# adc_420.net
KiCad netlist of a schematic drawn in Altium Designer
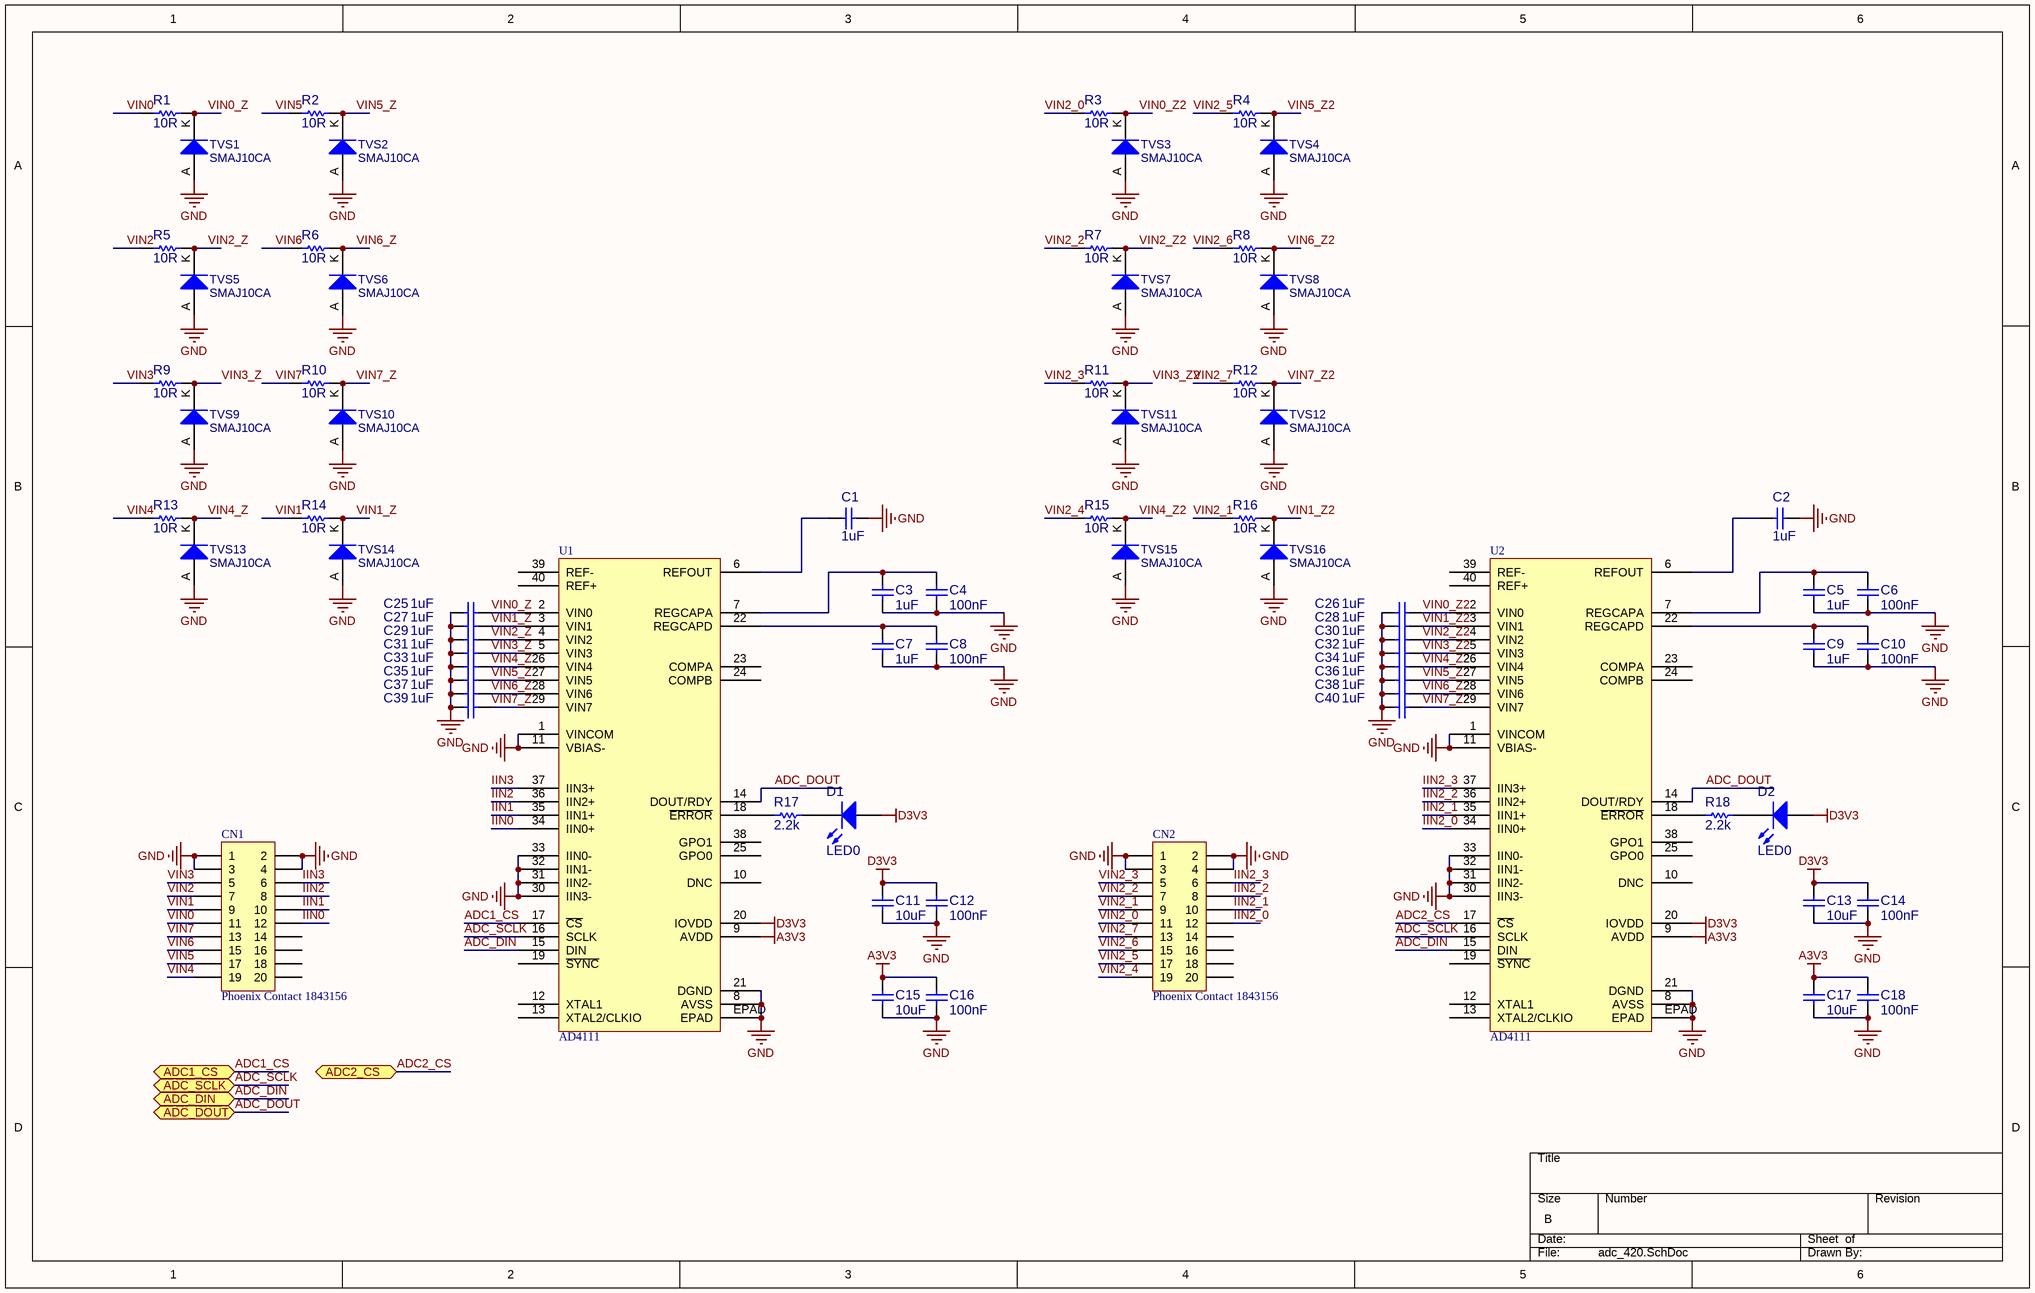
[diagram p0: adc_420.SchDoc]

(export (version "E")
  (design (tool "Eeschema 10.0.6"))
  (components
    (comp (ref "C1")
      (value "1uF")
      (footprint "C0603")
      (description "Capacitor")
      (fields (field (name "PUBLISHER") "Altium Limited"))
      (libsource (lib "Miscellaneous Devices") (part "Cap"))
    )
    (comp (ref "C2")
      (value "1uF")
      (footprint "C0603")
      (description "Capacitor")
      (fields (field (name "PUBLISHER") "Altium Limited"))
      (libsource (lib "Miscellaneous Devices") (part "Cap"))
    )
    (comp (ref "C3")
      (value "1uF")
      (footprint "C0603")
      (description "Capacitor")
      (fields (field (name "PUBLISHER") "Altium Limited"))
      (libsource (lib "Miscellaneous Devices") (part "Cap"))
    )
    (comp (ref "C4")
      (value "100nF")
      (footprint "C0603")
      (description "GRM155R71C104KA88J")
      (fields (field (name "PUBLISHER") "Altium Limited"))
      (libsource (lib "Miscellaneous Devices") (part "Cap"))
    )
    (comp (ref "C5")
      (value "1uF")
      (footprint "C0603")
      (description "Capacitor")
      (fields (field (name "PUBLISHER") "Altium Limited"))
      (libsource (lib "Miscellaneous Devices") (part "Cap"))
    )
    (comp (ref "C6")
      (value "100nF")
      (footprint "C0603")
      (description "GRM155R71C104KA88J")
      (fields (field (name "PUBLISHER") "Altium Limited"))
      (libsource (lib "Miscellaneous Devices") (part "Cap"))
    )
    (comp (ref "C7")
      (value "1uF")
      (footprint "C0603")
      (description "Capacitor")
      (fields (field (name "PUBLISHER") "Altium Limited"))
      (libsource (lib "Miscellaneous Devices") (part "Cap"))
    )
    (comp (ref "C8")
      (value "100nF")
      (footprint "C0603")
      (description "GRM155R71C104KA88J")
      (fields (field (name "PUBLISHER") "Altium Limited"))
      (libsource (lib "Miscellaneous Devices") (part "Cap"))
    )
    (comp (ref "C9")
      (value "1uF")
      (footprint "C0603")
      (description "Capacitor")
      (fields (field (name "PUBLISHER") "Altium Limited"))
      (libsource (lib "Miscellaneous Devices") (part "Cap"))
    )
    (comp (ref "C10")
      (value "100nF")
      (footprint "C0603")
      (description "GRM155R71C104KA88J")
      (fields (field (name "PUBLISHER") "Altium Limited"))
      (libsource (lib "Miscellaneous Devices") (part "Cap"))
    )
    (comp (ref "C11")
      (value "10uF")
      (footprint "C1206N")
      (description "Capacitor")
      (fields (field (name "PUBLISHER") "Altium Limited"))
      (libsource (lib "Miscellaneous Devices") (part "Cap"))
    )
    (comp (ref "C12")
      (value "100nF")
      (footprint "C0603")
      (description "GRM155R71C104KA88J")
      (fields (field (name "PUBLISHER") "Altium Limited"))
      (libsource (lib "Miscellaneous Devices") (part "Cap"))
    )
    (comp (ref "C13")
      (value "10uF")
      (footprint "C1206N")
      (description "Capacitor")
      (fields (field (name "PUBLISHER") "Altium Limited"))
      (libsource (lib "Miscellaneous Devices") (part "Cap"))
    )
    (comp (ref "C14")
      (value "100nF")
      (footprint "C0603")
      (description "GRM155R71C104KA88J")
      (fields (field (name "PUBLISHER") "Altium Limited"))
      (libsource (lib "Miscellaneous Devices") (part "Cap"))
    )
    (comp (ref "C15")
      (value "10uF")
      (footprint "C1206N")
      (description "Capacitor")
      (fields (field (name "PUBLISHER") "Altium Limited"))
      (libsource (lib "Miscellaneous Devices") (part "Cap"))
    )
    (comp (ref "C16")
      (value "100nF")
      (footprint "C0603")
      (description "GRM155R71C104KA88J")
      (fields (field (name "PUBLISHER") "Altium Limited"))
      (libsource (lib "Miscellaneous Devices") (part "Cap"))
    )
    (comp (ref "C17")
      (value "10uF")
      (footprint "C1206N")
      (description "Capacitor")
      (fields (field (name "PUBLISHER") "Altium Limited"))
      (libsource (lib "Miscellaneous Devices") (part "Cap"))
    )
    (comp (ref "C18")
      (value "100nF")
      (footprint "C0603")
      (description "GRM155R71C104KA88J")
      (fields (field (name "PUBLISHER") "Altium Limited"))
      (libsource (lib "Miscellaneous Devices") (part "Cap"))
    )
    (comp (ref "C25")
      (value "1uF")
      (footprint "C0603")
      (description "Capacitor")
      (fields (field (name "PUBLISHER") "Altium Limited"))
      (libsource (lib "Miscellaneous Devices") (part "Cap"))
    )
    (comp (ref "C26")
      (value "1uF")
      (footprint "C0603")
      (description "Capacitor")
      (fields (field (name "PUBLISHER") "Altium Limited"))
      (libsource (lib "Miscellaneous Devices") (part "Cap"))
    )
    (comp (ref "C27")
      (value "1uF")
      (footprint "C0603")
      (description "Capacitor")
      (fields (field (name "PUBLISHER") "Altium Limited"))
      (libsource (lib "Miscellaneous Devices") (part "Cap"))
    )
    (comp (ref "C28")
      (value "1uF")
      (footprint "C0603")
      (description "Capacitor")
      (fields (field (name "PUBLISHER") "Altium Limited"))
      (libsource (lib "Miscellaneous Devices") (part "Cap"))
    )
    (comp (ref "C29")
      (value "1uF")
      (footprint "C0603")
      (description "Capacitor")
      (fields (field (name "PUBLISHER") "Altium Limited"))
      (libsource (lib "Miscellaneous Devices") (part "Cap"))
    )
    (comp (ref "C30")
      (value "1uF")
      (footprint "C0603")
      (description "Capacitor")
      (fields (field (name "PUBLISHER") "Altium Limited"))
      (libsource (lib "Miscellaneous Devices") (part "Cap"))
    )
    (comp (ref "C31")
      (value "1uF")
      (footprint "C0603")
      (description "Capacitor")
      (fields (field (name "PUBLISHER") "Altium Limited"))
      (libsource (lib "Miscellaneous Devices") (part "Cap"))
    )
    (comp (ref "C32")
      (value "1uF")
      (footprint "C0603")
      (description "Capacitor")
      (fields (field (name "PUBLISHER") "Altium Limited"))
      (libsource (lib "Miscellaneous Devices") (part "Cap"))
    )
    (comp (ref "C33")
      (value "1uF")
      (footprint "C0603")
      (description "Capacitor")
      (fields (field (name "PUBLISHER") "Altium Limited"))
      (libsource (lib "Miscellaneous Devices") (part "Cap"))
    )
    (comp (ref "C34")
      (value "1uF")
      (footprint "C0603")
      (description "Capacitor")
      (fields (field (name "PUBLISHER") "Altium Limited"))
      (libsource (lib "Miscellaneous Devices") (part "Cap"))
    )
    (comp (ref "C35")
      (value "1uF")
      (footprint "C0603")
      (description "Capacitor")
      (fields (field (name "PUBLISHER") "Altium Limited"))
      (libsource (lib "Miscellaneous Devices") (part "Cap"))
    )
    (comp (ref "C36")
      (value "1uF")
      (footprint "C0603")
      (description "Capacitor")
      (fields (field (name "PUBLISHER") "Altium Limited"))
      (libsource (lib "Miscellaneous Devices") (part "Cap"))
    )
    (comp (ref "C37")
      (value "1uF")
      (footprint "C0603")
      (description "Capacitor")
      (fields (field (name "PUBLISHER") "Altium Limited"))
      (libsource (lib "Miscellaneous Devices") (part "Cap"))
    )
    (comp (ref "C38")
      (value "1uF")
      (footprint "C0603")
      (description "Capacitor")
      (fields (field (name "PUBLISHER") "Altium Limited"))
      (libsource (lib "Miscellaneous Devices") (part "Cap"))
    )
    (comp (ref "C39")
      (value "1uF")
      (footprint "C0603")
      (description "Capacitor")
      (fields (field (name "PUBLISHER") "Altium Limited"))
      (libsource (lib "Miscellaneous Devices") (part "Cap"))
    )
    (comp (ref "C40")
      (value "1uF")
      (footprint "C0603")
      (description "Capacitor")
      (fields (field (name "PUBLISHER") "Altium Limited"))
      (libsource (lib "Miscellaneous Devices") (part "Cap"))
    )
    (comp (ref "CN1")
      (value "Phoenix Contact 1843156")
      (footprint "PHOENIX1843156")
      (description "Header, 10-Pin, Dual row")
      (fields (field (name "PUBLISHER") "Altium Limited"))
      (libsource (lib "Miscellaneous Connectors") (part "Header 10X2"))
    )
    (comp (ref "CN2")
      (value "Phoenix Contact 1843156")
      (footprint "PHOENIX1843156")
      (description "Header, 10-Pin, Dual row")
      (fields (field (name "PUBLISHER") "Altium Limited"))
      (libsource (lib "Miscellaneous Connectors") (part "Header 10X2"))
    )
    (comp (ref "D1")
      (value "LED0")
      (footprint "LED0603")
      (description "Typical INFRARED GaAs LED")
      (fields (field (name "PUBLISHER") "Altium Limited"))
      (libsource (lib "Miscellaneous Devices") (part "LED0"))
    )
    (comp (ref "D2")
      (value "LED0")
      (footprint "LED0603")
      (description "Typical INFRARED GaAs LED")
      (fields (field (name "PUBLISHER") "Altium Limited"))
      (libsource (lib "Miscellaneous Devices") (part "LED0"))
    )
    (comp (ref "R1")
      (value "10R")
      (footprint "R0603")
      (description "Resistor")
      (fields (field (name "PUBLISHER") "Altium Limited"))
      (libsource (lib "Miscellaneous Devices") (part "Res1"))
    )
    (comp (ref "R2")
      (value "10R")
      (footprint "R0603")
      (description "Resistor")
      (fields (field (name "PUBLISHER") "Altium Limited"))
      (libsource (lib "Miscellaneous Devices") (part "Res1"))
    )
    (comp (ref "R3")
      (value "10R")
      (footprint "R0603")
      (description "Resistor")
      (fields (field (name "PUBLISHER") "Altium Limited"))
      (libsource (lib "Miscellaneous Devices") (part "Res1"))
    )
    (comp (ref "R4")
      (value "10R")
      (footprint "R0603")
      (description "Resistor")
      (fields (field (name "PUBLISHER") "Altium Limited"))
      (libsource (lib "Miscellaneous Devices") (part "Res1"))
    )
    (comp (ref "R5")
      (value "10R")
      (footprint "R0603")
      (description "Resistor")
      (fields (field (name "PUBLISHER") "Altium Limited"))
      (libsource (lib "Miscellaneous Devices") (part "Res1"))
    )
    (comp (ref "R6")
      (value "10R")
      (footprint "R0603")
      (description "Resistor")
      (fields (field (name "PUBLISHER") "Altium Limited"))
      (libsource (lib "Miscellaneous Devices") (part "Res1"))
    )
    (comp (ref "R7")
      (value "10R")
      (footprint "R0603")
      (description "Resistor")
      (fields (field (name "PUBLISHER") "Altium Limited"))
      (libsource (lib "Miscellaneous Devices") (part "Res1"))
    )
    (comp (ref "R8")
      (value "10R")
      (footprint "R0603")
      (description "Resistor")
      (fields (field (name "PUBLISHER") "Altium Limited"))
      (libsource (lib "Miscellaneous Devices") (part "Res1"))
    )
    (comp (ref "R9")
      (value "10R")
      (footprint "R0603")
      (description "Resistor")
      (fields (field (name "PUBLISHER") "Altium Limited"))
      (libsource (lib "Miscellaneous Devices") (part "Res1"))
    )
    (comp (ref "R10")
      (value "10R")
      (footprint "R0603")
      (description "Resistor")
      (fields (field (name "PUBLISHER") "Altium Limited"))
      (libsource (lib "Miscellaneous Devices") (part "Res1"))
    )
    (comp (ref "R11")
      (value "10R")
      (footprint "R0603")
      (description "Resistor")
      (fields (field (name "PUBLISHER") "Altium Limited"))
      (libsource (lib "Miscellaneous Devices") (part "Res1"))
    )
    (comp (ref "R12")
      (value "10R")
      (footprint "R0603")
      (description "Resistor")
      (fields (field (name "PUBLISHER") "Altium Limited"))
      (libsource (lib "Miscellaneous Devices") (part "Res1"))
    )
    (comp (ref "R13")
      (value "10R")
      (footprint "R0603")
      (description "Resistor")
      (fields (field (name "PUBLISHER") "Altium Limited"))
      (libsource (lib "Miscellaneous Devices") (part "Res1"))
    )
    (comp (ref "R14")
      (value "10R")
      (footprint "R0603")
      (description "Resistor")
      (fields (field (name "PUBLISHER") "Altium Limited"))
      (libsource (lib "Miscellaneous Devices") (part "Res1"))
    )
    (comp (ref "R15")
      (value "10R")
      (footprint "R0603")
      (description "Resistor")
      (fields (field (name "PUBLISHER") "Altium Limited"))
      (libsource (lib "Miscellaneous Devices") (part "Res1"))
    )
    (comp (ref "R16")
      (value "10R")
      (footprint "R0603")
      (description "Resistor")
      (fields (field (name "PUBLISHER") "Altium Limited"))
      (libsource (lib "Miscellaneous Devices") (part "Res1"))
    )
    (comp (ref "R17")
      (value "2.2k")
      (footprint "R0603")
      (description "Resistor")
      (fields (field (name "PUBLISHER") "Altium Limited"))
      (libsource (lib "Miscellaneous Devices") (part "Res1"))
    )
    (comp (ref "R18")
      (value "2.2k")
      (footprint "R0603")
      (description "Resistor")
      (fields (field (name "PUBLISHER") "Altium Limited"))
      (libsource (lib "Miscellaneous Devices") (part "Res1"))
    )
    (comp (ref "TVS1") (value "SMAJ10CA") (footprint "SMA") (libsource (lib "ADI-MEMs-more") (part "DIODE")))
    (comp (ref "TVS2") (value "SMAJ10CA") (footprint "SMA") (libsource (lib "ADI-MEMs-more") (part "DIODE")))
    (comp (ref "TVS3") (value "SMAJ10CA") (footprint "SMA") (libsource (lib "ADI-MEMs-more") (part "DIODE")))
    (comp (ref "TVS4") (value "SMAJ10CA") (footprint "SMA") (libsource (lib "ADI-MEMs-more") (part "DIODE")))
    (comp (ref "TVS5") (value "SMAJ10CA") (footprint "SMA") (libsource (lib "ADI-MEMs-more") (part "DIODE")))
    (comp (ref "TVS6") (value "SMAJ10CA") (footprint "SMA") (libsource (lib "ADI-MEMs-more") (part "DIODE")))
    (comp (ref "TVS7") (value "SMAJ10CA") (footprint "SMA") (libsource (lib "ADI-MEMs-more") (part "DIODE")))
    (comp (ref "TVS8") (value "SMAJ10CA") (footprint "SMA") (libsource (lib "ADI-MEMs-more") (part "DIODE")))
    (comp (ref "TVS9") (value "SMAJ10CA") (footprint "SMA") (libsource (lib "ADI-MEMs-more") (part "DIODE")))
    (comp (ref "TVS10") (value "SMAJ10CA") (footprint "SMA") (libsource (lib "ADI-MEMs-more") (part "DIODE")))
    (comp (ref "TVS11") (value "SMAJ10CA") (footprint "SMA") (libsource (lib "ADI-MEMs-more") (part "DIODE")))
    (comp (ref "TVS12") (value "SMAJ10CA") (footprint "SMA") (libsource (lib "ADI-MEMs-more") (part "DIODE")))
    (comp (ref "TVS13") (value "SMAJ10CA") (footprint "SMA") (libsource (lib "ADI-MEMs-more") (part "DIODE")))
    (comp (ref "TVS14") (value "SMAJ10CA") (footprint "SMA") (libsource (lib "ADI-MEMs-more") (part "DIODE")))
    (comp (ref "TVS15") (value "SMAJ10CA") (footprint "SMA") (libsource (lib "ADI-MEMs-more") (part "DIODE")))
    (comp (ref "TVS16") (value "SMAJ10CA") (footprint "SMA") (libsource (lib "ADI-MEMs-more") (part "DIODE")))
    (comp (ref "U1")
      (value "AD4111")
      (footprint "AD7119")
      (libsource (lib "PowerComps-more") (part "AD4111"))
    )
    (comp (ref "U2")
      (value "AD4111")
      (footprint "AD7119")
      (libsource (lib "PowerComps-more") (part "AD4111"))
    )
  )
  (nets
    (net (code "1") (name "/ADC1_CS") (class "Default")
      (node (ref "U1") (pin "17") (pinfunction "~{CS}_17") (pintype "passive"))
    )
    (net (code "2") (name "/ADC2_CS") (class "Default")
      (node (ref "U2") (pin "17") (pinfunction "~{CS}_17") (pintype "passive"))
    )
    (net (code "3") (name "/ADC_DIN") (class "Default")
      (node (ref "U1") (pin "15") (pinfunction "DIN_15") (pintype "passive"))
      (node (ref "U2") (pin "15") (pinfunction "DIN_15") (pintype "passive"))
    )
    (net (code "4") (name "/ADC_DOUT") (class "Default")
      (node (ref "U1") (pin "14") (pinfunction "DOUT/RDY_14") (pintype "passive"))
      (node (ref "U2") (pin "14") (pinfunction "DOUT/RDY_14") (pintype "passive"))
    )
    (net (code "5") (name "/ADC_SCLK") (class "Default")
      (node (ref "U1") (pin "16") (pinfunction "SCLK_16") (pintype "passive"))
      (node (ref "U2") (pin "16") (pinfunction "SCLK_16") (pintype "passive"))
    )
    (net (code "6") (name "/IIN0") (class "Default")
      (node (ref "CN1") (pin "12") (pinfunction "12_12") (pintype "passive"))
      (node (ref "U1") (pin "34") (pinfunction "IIN0+_34") (pintype "passive"))
    )
    (net (code "7") (name "/IIN1") (class "Default")
      (node (ref "CN1") (pin "10") (pinfunction "10_10") (pintype "passive"))
      (node (ref "U1") (pin "35") (pinfunction "IIN1+_35") (pintype "passive"))
    )
    (net (code "8") (name "/IIN2") (class "Default")
      (node (ref "CN1") (pin "8") (pinfunction "8_8") (pintype "passive"))
      (node (ref "U1") (pin "36") (pinfunction "IIN2+_36") (pintype "passive"))
    )
    (net (code "9") (name "/IIN2_0") (class "Default")
      (node (ref "CN2") (pin "12") (pinfunction "12_12") (pintype "passive"))
      (node (ref "U2") (pin "34") (pinfunction "IIN0+_34") (pintype "passive"))
    )
    (net (code "10") (name "/IIN2_1") (class "Default")
      (node (ref "CN2") (pin "10") (pinfunction "10_10") (pintype "passive"))
      (node (ref "U2") (pin "35") (pinfunction "IIN1+_35") (pintype "passive"))
    )
    (net (code "11") (name "/IIN2_2") (class "Default")
      (node (ref "CN2") (pin "8") (pinfunction "8_8") (pintype "passive"))
      (node (ref "U2") (pin "36") (pinfunction "IIN2+_36") (pintype "passive"))
    )
    (net (code "12") (name "/IIN2_3") (class "Default")
      (node (ref "CN2") (pin "6") (pinfunction "6_6") (pintype "passive"))
      (node (ref "U2") (pin "37") (pinfunction "IIN3+_37") (pintype "passive"))
    )
    (net (code "13") (name "/IIN3") (class "Default")
      (node (ref "CN1") (pin "6") (pinfunction "6_6") (pintype "passive"))
      (node (ref "U1") (pin "37") (pinfunction "IIN3+_37") (pintype "passive"))
    )
    (net (code "14") (name "/VIN0") (class "Default")
      (node (ref "CN1") (pin "11") (pinfunction "11_11") (pintype "passive"))
      (node (ref "R1") (pin "1") (pinfunction "1_1") (pintype "passive"))
    )
    (net (code "15") (name "/VIN0_Z") (class "Default")
      (node (ref "C25") (pin "2") (pinfunction "2_2") (pintype "passive"))
      (node (ref "R1") (pin "2") (pinfunction "2_2") (pintype "passive"))
      (node (ref "TVS1") (pin "K") (pintype "passive"))
      (node (ref "U1") (pin "2") (pinfunction "VIN0_2") (pintype "passive"))
    )
    (net (code "16") (name "/VIN0_Z2") (class "Default")
      (node (ref "C26") (pin "2") (pinfunction "2_2") (pintype "passive"))
      (node (ref "R3") (pin "2") (pinfunction "2_2") (pintype "passive"))
      (node (ref "TVS3") (pin "K") (pintype "passive"))
      (node (ref "U2") (pin "2") (pinfunction "VIN0_2") (pintype "passive"))
    )
    (net (code "17") (name "/VIN1") (class "Default")
      (node (ref "CN1") (pin "9") (pinfunction "9_9") (pintype "passive"))
      (node (ref "R14") (pin "1") (pinfunction "1_1") (pintype "passive"))
    )
    (net (code "18") (name "/VIN1_Z") (class "Default")
      (node (ref "C27") (pin "2") (pinfunction "2_2") (pintype "passive"))
      (node (ref "R14") (pin "2") (pinfunction "2_2") (pintype "passive"))
      (node (ref "TVS14") (pin "K") (pintype "passive"))
      (node (ref "U1") (pin "3") (pinfunction "VIN1_3") (pintype "passive"))
    )
    (net (code "19") (name "/VIN1_Z2") (class "Default")
      (node (ref "C28") (pin "2") (pinfunction "2_2") (pintype "passive"))
      (node (ref "R16") (pin "2") (pinfunction "2_2") (pintype "passive"))
      (node (ref "TVS16") (pin "K") (pintype "passive"))
      (node (ref "U2") (pin "3") (pinfunction "VIN1_3") (pintype "passive"))
    )
    (net (code "20") (name "/VIN2") (class "Default")
      (node (ref "CN1") (pin "7") (pinfunction "7_7") (pintype "passive"))
      (node (ref "R5") (pin "1") (pinfunction "1_1") (pintype "passive"))
    )
    (net (code "21") (name "/VIN2_0") (class "Default")
      (node (ref "CN2") (pin "11") (pinfunction "11_11") (pintype "passive"))
      (node (ref "R3") (pin "1") (pinfunction "1_1") (pintype "passive"))
    )
    (net (code "22") (name "/VIN2_1") (class "Default")
      (node (ref "CN2") (pin "9") (pinfunction "9_9") (pintype "passive"))
      (node (ref "R16") (pin "1") (pinfunction "1_1") (pintype "passive"))
    )
    (net (code "23") (name "/VIN2_2") (class "Default")
      (node (ref "CN2") (pin "7") (pinfunction "7_7") (pintype "passive"))
      (node (ref "R7") (pin "1") (pinfunction "1_1") (pintype "passive"))
    )
    (net (code "24") (name "/VIN2_3") (class "Default")
      (node (ref "CN2") (pin "5") (pinfunction "5_5") (pintype "passive"))
      (node (ref "R11") (pin "1") (pinfunction "1_1") (pintype "passive"))
    )
    (net (code "25") (name "/VIN2_4") (class "Default")
      (node (ref "CN2") (pin "19") (pinfunction "19_19") (pintype "passive"))
      (node (ref "R15") (pin "1") (pinfunction "1_1") (pintype "passive"))
    )
    (net (code "26") (name "/VIN2_5") (class "Default")
      (node (ref "CN2") (pin "17") (pinfunction "17_17") (pintype "passive"))
      (node (ref "R4") (pin "1") (pinfunction "1_1") (pintype "passive"))
    )
    (net (code "27") (name "/VIN2_6") (class "Default")
      (node (ref "CN2") (pin "15") (pinfunction "15_15") (pintype "passive"))
      (node (ref "R8") (pin "1") (pinfunction "1_1") (pintype "passive"))
    )
    (net (code "28") (name "/VIN2_7") (class "Default")
      (node (ref "CN2") (pin "13") (pinfunction "13_13") (pintype "passive"))
      (node (ref "R12") (pin "1") (pinfunction "1_1") (pintype "passive"))
    )
    (net (code "29") (name "/VIN2_Z") (class "Default")
      (node (ref "C29") (pin "2") (pinfunction "2_2") (pintype "passive"))
      (node (ref "R5") (pin "2") (pinfunction "2_2") (pintype "passive"))
      (node (ref "TVS5") (pin "K") (pintype "passive"))
      (node (ref "U1") (pin "4") (pinfunction "VIN2_4") (pintype "passive"))
    )
    (net (code "30") (name "/VIN2_Z2") (class "Default")
      (node (ref "C30") (pin "2") (pinfunction "2_2") (pintype "passive"))
      (node (ref "R7") (pin "2") (pinfunction "2_2") (pintype "passive"))
      (node (ref "TVS7") (pin "K") (pintype "passive"))
      (node (ref "U2") (pin "4") (pinfunction "VIN2_4") (pintype "passive"))
    )
    (net (code "31") (name "/VIN3") (class "Default")
      (node (ref "CN1") (pin "5") (pinfunction "5_5") (pintype "passive"))
      (node (ref "R9") (pin "1") (pinfunction "1_1") (pintype "passive"))
    )
    (net (code "32") (name "/VIN3_Z") (class "Default")
      (node (ref "C31") (pin "2") (pinfunction "2_2") (pintype "passive"))
      (node (ref "R9") (pin "2") (pinfunction "2_2") (pintype "passive"))
      (node (ref "TVS9") (pin "K") (pintype "passive"))
      (node (ref "U1") (pin "5") (pinfunction "VIN3_5") (pintype "passive"))
    )
    (net (code "33") (name "/VIN3_Z2") (class "Default")
      (node (ref "C32") (pin "2") (pinfunction "2_2") (pintype "passive"))
      (node (ref "R11") (pin "2") (pinfunction "2_2") (pintype "passive"))
      (node (ref "TVS11") (pin "K") (pintype "passive"))
      (node (ref "U2") (pin "5") (pinfunction "VIN3_5") (pintype "passive"))
    )
    (net (code "34") (name "/VIN4") (class "Default")
      (node (ref "CN1") (pin "19") (pinfunction "19_19") (pintype "passive"))
      (node (ref "R13") (pin "1") (pinfunction "1_1") (pintype "passive"))
    )
    (net (code "35") (name "/VIN4_Z") (class "Default")
      (node (ref "C33") (pin "2") (pinfunction "2_2") (pintype "passive"))
      (node (ref "R13") (pin "2") (pinfunction "2_2") (pintype "passive"))
      (node (ref "TVS13") (pin "K") (pintype "passive"))
      (node (ref "U1") (pin "26") (pinfunction "VIN4_26") (pintype "passive"))
    )
    (net (code "36") (name "/VIN4_Z2") (class "Default")
      (node (ref "C34") (pin "2") (pinfunction "2_2") (pintype "passive"))
      (node (ref "R15") (pin "2") (pinfunction "2_2") (pintype "passive"))
      (node (ref "TVS15") (pin "K") (pintype "passive"))
      (node (ref "U2") (pin "26") (pinfunction "VIN4_26") (pintype "passive"))
    )
    (net (code "37") (name "/VIN5") (class "Default")
      (node (ref "CN1") (pin "17") (pinfunction "17_17") (pintype "passive"))
      (node (ref "R2") (pin "1") (pinfunction "1_1") (pintype "passive"))
    )
    (net (code "38") (name "/VIN5_Z") (class "Default")
      (node (ref "C35") (pin "2") (pinfunction "2_2") (pintype "passive"))
      (node (ref "R2") (pin "2") (pinfunction "2_2") (pintype "passive"))
      (node (ref "TVS2") (pin "K") (pintype "passive"))
      (node (ref "U1") (pin "27") (pinfunction "VIN5_27") (pintype "passive"))
    )
    (net (code "39") (name "/VIN5_Z2") (class "Default")
      (node (ref "C36") (pin "2") (pinfunction "2_2") (pintype "passive"))
      (node (ref "R4") (pin "2") (pinfunction "2_2") (pintype "passive"))
      (node (ref "TVS4") (pin "K") (pintype "passive"))
      (node (ref "U2") (pin "27") (pinfunction "VIN5_27") (pintype "passive"))
    )
    (net (code "40") (name "/VIN6") (class "Default")
      (node (ref "CN1") (pin "15") (pinfunction "15_15") (pintype "passive"))
      (node (ref "R6") (pin "1") (pinfunction "1_1") (pintype "passive"))
    )
    (net (code "41") (name "/VIN6_Z") (class "Default")
      (node (ref "C37") (pin "2") (pinfunction "2_2") (pintype "passive"))
      (node (ref "R6") (pin "2") (pinfunction "2_2") (pintype "passive"))
      (node (ref "TVS6") (pin "K") (pintype "passive"))
      (node (ref "U1") (pin "28") (pinfunction "VIN6_28") (pintype "passive"))
    )
    (net (code "42") (name "/VIN6_Z2") (class "Default")
      (node (ref "C38") (pin "2") (pinfunction "2_2") (pintype "passive"))
      (node (ref "R8") (pin "2") (pinfunction "2_2") (pintype "passive"))
      (node (ref "TVS8") (pin "K") (pintype "passive"))
      (node (ref "U2") (pin "28") (pinfunction "VIN6_28") (pintype "passive"))
    )
    (net (code "43") (name "/VIN7") (class "Default")
      (node (ref "CN1") (pin "13") (pinfunction "13_13") (pintype "passive"))
      (node (ref "R10") (pin "1") (pinfunction "1_1") (pintype "passive"))
    )
    (net (code "44") (name "/VIN7_Z") (class "Default")
      (node (ref "C39") (pin "2") (pinfunction "2_2") (pintype "passive"))
      (node (ref "R10") (pin "2") (pinfunction "2_2") (pintype "passive"))
      (node (ref "TVS10") (pin "K") (pintype "passive"))
      (node (ref "U1") (pin "29") (pinfunction "VIN7_29") (pintype "passive"))
    )
    (net (code "45") (name "/VIN7_Z2") (class "Default")
      (node (ref "C40") (pin "2") (pinfunction "2_2") (pintype "passive"))
      (node (ref "R12") (pin "2") (pinfunction "2_2") (pintype "passive"))
      (node (ref "TVS12") (pin "K") (pintype "passive"))
      (node (ref "U2") (pin "29") (pinfunction "VIN7_29") (pintype "passive"))
    )
    (net (code "46") (name "A3V3") (class "Default")
      (node (ref "C15") (pin "1") (pinfunction "1_1") (pintype "passive"))
      (node (ref "C16") (pin "1") (pinfunction "1_1") (pintype "passive"))
      (node (ref "C17") (pin "1") (pinfunction "1_1") (pintype "passive"))
      (node (ref "C18") (pin "1") (pinfunction "1_1") (pintype "passive"))
      (node (ref "U1") (pin "9") (pinfunction "AVDD_9") (pintype "passive"))
      (node (ref "U2") (pin "9") (pinfunction "AVDD_9") (pintype "passive"))
    )
    (net (code "47") (name "D3V3") (class "Default")
      (node (ref "C11") (pin "1") (pinfunction "1_1") (pintype "passive"))
      (node (ref "C12") (pin "1") (pinfunction "1_1") (pintype "passive"))
      (node (ref "C13") (pin "1") (pinfunction "1_1") (pintype "passive"))
      (node (ref "C14") (pin "1") (pinfunction "1_1") (pintype "passive"))
      (node (ref "D1") (pin "1") (pinfunction "A_1") (pintype "passive"))
      (node (ref "D2") (pin "1") (pinfunction "A_1") (pintype "passive"))
      (node (ref "U1") (pin "20") (pinfunction "IOVDD_20") (pintype "passive"))
      (node (ref "U2") (pin "20") (pinfunction "IOVDD_20") (pintype "passive"))
    )
    (net (code "48") (name "GND") (class "Default")
      (node (ref "C1") (pin "2") (pinfunction "2_2") (pintype "passive"))
      (node (ref "C10") (pin "2") (pinfunction "2_2") (pintype "passive"))
      (node (ref "C11") (pin "2") (pinfunction "2_2") (pintype "passive"))
      (node (ref "C12") (pin "2") (pinfunction "2_2") (pintype "passive"))
      (node (ref "C13") (pin "2") (pinfunction "2_2") (pintype "passive"))
      (node (ref "C14") (pin "2") (pinfunction "2_2") (pintype "passive"))
      (node (ref "C15") (pin "2") (pinfunction "2_2") (pintype "passive"))
      (node (ref "C16") (pin "2") (pinfunction "2_2") (pintype "passive"))
      (node (ref "C17") (pin "2") (pinfunction "2_2") (pintype "passive"))
      (node (ref "C18") (pin "2") (pinfunction "2_2") (pintype "passive"))
      (node (ref "C2") (pin "2") (pinfunction "2_2") (pintype "passive"))
      (node (ref "C25") (pin "1") (pinfunction "1_1") (pintype "passive"))
      (node (ref "C26") (pin "1") (pinfunction "1_1") (pintype "passive"))
      (node (ref "C27") (pin "1") (pinfunction "1_1") (pintype "passive"))
      (node (ref "C28") (pin "1") (pinfunction "1_1") (pintype "passive"))
      (node (ref "C29") (pin "1") (pinfunction "1_1") (pintype "passive"))
      (node (ref "C3") (pin "2") (pinfunction "2_2") (pintype "passive"))
      (node (ref "C30") (pin "1") (pinfunction "1_1") (pintype "passive"))
      (node (ref "C31") (pin "1") (pinfunction "1_1") (pintype "passive"))
      (node (ref "C32") (pin "1") (pinfunction "1_1") (pintype "passive"))
      (node (ref "C33") (pin "1") (pinfunction "1_1") (pintype "passive"))
      (node (ref "C34") (pin "1") (pinfunction "1_1") (pintype "passive"))
      (node (ref "C35") (pin "1") (pinfunction "1_1") (pintype "passive"))
      (node (ref "C36") (pin "1") (pinfunction "1_1") (pintype "passive"))
      (node (ref "C37") (pin "1") (pinfunction "1_1") (pintype "passive"))
      (node (ref "C38") (pin "1") (pinfunction "1_1") (pintype "passive"))
      (node (ref "C39") (pin "1") (pinfunction "1_1") (pintype "passive"))
      (node (ref "C4") (pin "2") (pinfunction "2_2") (pintype "passive"))
      (node (ref "C40") (pin "1") (pinfunction "1_1") (pintype "passive"))
      (node (ref "C5") (pin "2") (pinfunction "2_2") (pintype "passive"))
      (node (ref "C6") (pin "2") (pinfunction "2_2") (pintype "passive"))
      (node (ref "C7") (pin "2") (pinfunction "2_2") (pintype "passive"))
      (node (ref "C8") (pin "2") (pinfunction "2_2") (pintype "passive"))
      (node (ref "C9") (pin "2") (pinfunction "2_2") (pintype "passive"))
      (node (ref "CN1") (pin "1") (pinfunction "1_1") (pintype "passive"))
      (node (ref "CN1") (pin "2") (pinfunction "2_2") (pintype "passive"))
      (node (ref "CN1") (pin "3") (pinfunction "3_3") (pintype "passive"))
      (node (ref "CN1") (pin "4") (pinfunction "4_4") (pintype "passive"))
      (node (ref "CN2") (pin "1") (pinfunction "1_1") (pintype "passive"))
      (node (ref "CN2") (pin "2") (pinfunction "2_2") (pintype "passive"))
      (node (ref "CN2") (pin "3") (pinfunction "3_3") (pintype "passive"))
      (node (ref "CN2") (pin "4") (pinfunction "4_4") (pintype "passive"))
      (node (ref "TVS1") (pin "A") (pintype "passive"))
      (node (ref "TVS10") (pin "A") (pintype "passive"))
      (node (ref "TVS11") (pin "A") (pintype "passive"))
      (node (ref "TVS12") (pin "A") (pintype "passive"))
      (node (ref "TVS13") (pin "A") (pintype "passive"))
      (node (ref "TVS14") (pin "A") (pintype "passive"))
      (node (ref "TVS15") (pin "A") (pintype "passive"))
      (node (ref "TVS16") (pin "A") (pintype "passive"))
      (node (ref "TVS2") (pin "A") (pintype "passive"))
      (node (ref "TVS3") (pin "A") (pintype "passive"))
      (node (ref "TVS4") (pin "A") (pintype "passive"))
      (node (ref "TVS5") (pin "A") (pintype "passive"))
      (node (ref "TVS6") (pin "A") (pintype "passive"))
      (node (ref "TVS7") (pin "A") (pintype "passive"))
      (node (ref "TVS8") (pin "A") (pintype "passive"))
      (node (ref "TVS9") (pin "A") (pintype "passive"))
      (node (ref "U1") (pin "1") (pinfunction "VINCOM_1") (pintype "passive"))
      (node (ref "U1") (pin "11") (pinfunction "VBIAS-_11") (pintype "passive"))
      (node (ref "U1") (pin "21") (pinfunction "DGND_21") (pintype "passive"))
      (node (ref "U1") (pin "30") (pinfunction "IIN3-_30") (pintype "passive"))
      (node (ref "U1") (pin "31") (pinfunction "IIN2-_31") (pintype "passive"))
      (node (ref "U1") (pin "32") (pinfunction "IIN1-_32") (pintype "passive"))
      (node (ref "U1") (pin "33") (pinfunction "IIN0-_33") (pintype "passive"))
      (node (ref "U1") (pin "8") (pinfunction "AVSS_8") (pintype "passive"))
      (node (ref "U1") (pin "EPAD") (pinfunction "EPAD_EPAD") (pintype "passive"))
      (node (ref "U2") (pin "1") (pinfunction "VINCOM_1") (pintype "passive"))
      (node (ref "U2") (pin "11") (pinfunction "VBIAS-_11") (pintype "passive"))
      (node (ref "U2") (pin "21") (pinfunction "DGND_21") (pintype "passive"))
      (node (ref "U2") (pin "30") (pinfunction "IIN3-_30") (pintype "passive"))
      (node (ref "U2") (pin "31") (pinfunction "IIN2-_31") (pintype "passive"))
      (node (ref "U2") (pin "32") (pinfunction "IIN1-_32") (pintype "passive"))
      (node (ref "U2") (pin "33") (pinfunction "IIN0-_33") (pintype "passive"))
      (node (ref "U2") (pin "8") (pinfunction "AVSS_8") (pintype "passive"))
      (node (ref "U2") (pin "EPAD") (pinfunction "EPAD_EPAD") (pintype "passive"))
    )
    (net (code "49") (name "Net-(D1-K)") (class "Default")
      (node (ref "D1") (pin "2") (pinfunction "K_2") (pintype "passive"))
      (node (ref "R17") (pin "2") (pinfunction "2_2") (pintype "passive"))
    )
    (net (code "50") (name "Net-(D2-K)") (class "Default")
      (node (ref "D2") (pin "2") (pinfunction "K_2") (pintype "passive"))
      (node (ref "R18") (pin "2") (pinfunction "2_2") (pintype "passive"))
    )
    (net (code "51") (name "Net-(U1-REFOUT)") (class "Default")
      (node (ref "C1") (pin "1") (pinfunction "1_1") (pintype "passive"))
      (node (ref "U1") (pin "6") (pinfunction "REFOUT_6") (pintype "passive"))
    )
    (net (code "52") (name "Net-(U1-REGCAPA)") (class "Default")
      (node (ref "C3") (pin "1") (pinfunction "1_1") (pintype "passive"))
      (node (ref "C4") (pin "1") (pinfunction "1_1") (pintype "passive"))
      (node (ref "U1") (pin "7") (pinfunction "REGCAPA_7") (pintype "passive"))
    )
    (net (code "53") (name "Net-(U1-REGCAPD)") (class "Default")
      (node (ref "C7") (pin "1") (pinfunction "1_1") (pintype "passive"))
      (node (ref "C8") (pin "1") (pinfunction "1_1") (pintype "passive"))
      (node (ref "U1") (pin "22") (pinfunction "REGCAPD_22") (pintype "passive"))
    )
    (net (code "54") (name "Net-(U1-~{ERROR})") (class "Default")
      (node (ref "R17") (pin "1") (pinfunction "1_1") (pintype "passive"))
      (node (ref "U1") (pin "18") (pinfunction "~{ERROR}_18") (pintype "passive"))
    )
    (net (code "55") (name "Net-(U2-REFOUT)") (class "Default")
      (node (ref "C2") (pin "1") (pinfunction "1_1") (pintype "passive"))
      (node (ref "U2") (pin "6") (pinfunction "REFOUT_6") (pintype "passive"))
    )
    (net (code "56") (name "Net-(U2-REGCAPA)") (class "Default")
      (node (ref "C5") (pin "1") (pinfunction "1_1") (pintype "passive"))
      (node (ref "C6") (pin "1") (pinfunction "1_1") (pintype "passive"))
      (node (ref "U2") (pin "7") (pinfunction "REGCAPA_7") (pintype "passive"))
    )
    (net (code "57") (name "Net-(U2-REGCAPD)") (class "Default")
      (node (ref "C10") (pin "1") (pinfunction "1_1") (pintype "passive"))
      (node (ref "C9") (pin "1") (pinfunction "1_1") (pintype "passive"))
      (node (ref "U2") (pin "22") (pinfunction "REGCAPD_22") (pintype "passive"))
    )
    (net (code "58") (name "Net-(U2-~{ERROR})") (class "Default")
      (node (ref "R18") (pin "1") (pinfunction "1_1") (pintype "passive"))
      (node (ref "U2") (pin "18") (pinfunction "~{ERROR}_18") (pintype "passive"))
    )
    (net (code "59") (name "unconnected-(CN1-Pad14)") (class "Default")
      (node (ref "CN1") (pin "14") (pinfunction "14_14") (pintype "passive"))
    )
    (net (code "60") (name "unconnected-(CN1-Pad16)") (class "Default")
      (node (ref "CN1") (pin "16") (pinfunction "16_16") (pintype "passive"))
    )
    (net (code "61") (name "unconnected-(CN1-Pad18)") (class "Default")
      (node (ref "CN1") (pin "18") (pinfunction "18_18") (pintype "passive"))
    )
    (net (code "62") (name "unconnected-(CN1-Pad20)") (class "Default")
      (node (ref "CN1") (pin "20") (pinfunction "20_20") (pintype "passive"))
    )
    (net (code "63") (name "unconnected-(CN2-Pad14)") (class "Default")
      (node (ref "CN2") (pin "14") (pinfunction "14_14") (pintype "passive"))
    )
    (net (code "64") (name "unconnected-(CN2-Pad16)") (class "Default")
      (node (ref "CN2") (pin "16") (pinfunction "16_16") (pintype "passive"))
    )
    (net (code "65") (name "unconnected-(CN2-Pad18)") (class "Default")
      (node (ref "CN2") (pin "18") (pinfunction "18_18") (pintype "passive"))
    )
    (net (code "66") (name "unconnected-(CN2-Pad20)") (class "Default")
      (node (ref "CN2") (pin "20") (pinfunction "20_20") (pintype "passive"))
    )
    (net (code "67") (name "unconnected-(U1-COMPA-Pad23)") (class "Default")
      (node (ref "U1") (pin "23") (pinfunction "COMPA_23") (pintype "passive"))
    )
    (net (code "68") (name "unconnected-(U1-COMPB-Pad24)") (class "Default")
      (node (ref "U1") (pin "24") (pinfunction "COMPB_24") (pintype "passive"))
    )
    (net (code "69") (name "unconnected-(U1-DNC-Pad10)") (class "Default")
      (node (ref "U1") (pin "10") (pinfunction "DNC_10") (pintype "passive"))
    )
    (net (code "70") (name "unconnected-(U1-GPO0-Pad25)") (class "Default")
      (node (ref "U1") (pin "25") (pinfunction "GPO0_25") (pintype "passive"))
    )
    (net (code "71") (name "unconnected-(U1-GPO1-Pad38)") (class "Default")
      (node (ref "U1") (pin "38") (pinfunction "GPO1_38") (pintype "passive"))
    )
    (net (code "72") (name "unconnected-(U1-REF+-Pad40)") (class "Default")
      (node (ref "U1") (pin "40") (pinfunction "REF+_40") (pintype "passive"))
    )
    (net (code "73") (name "unconnected-(U1-REF--Pad39)") (class "Default")
      (node (ref "U1") (pin "39") (pinfunction "REF-_39") (pintype "passive"))
    )
    (net (code "74") (name "unconnected-(U1-XTAL1-Pad12)") (class "Default")
      (node (ref "U1") (pin "12") (pinfunction "XTAL1_12") (pintype "passive"))
    )
    (net (code "75") (name "unconnected-(U1-XTAL2{slash}CLKIO-Pad13)") (class "Default")
      (node (ref "U1") (pin "13") (pinfunction "XTAL2/CLKIO_13") (pintype "passive"))
    )
    (net (code "76") (name "unconnected-(U1-~{SYNC}-Pad19)") (class "Default")
      (node (ref "U1") (pin "19") (pinfunction "~{SYNC}_19") (pintype "passive"))
    )
    (net (code "77") (name "unconnected-(U2-COMPA-Pad23)") (class "Default")
      (node (ref "U2") (pin "23") (pinfunction "COMPA_23") (pintype "passive"))
    )
    (net (code "78") (name "unconnected-(U2-COMPB-Pad24)") (class "Default")
      (node (ref "U2") (pin "24") (pinfunction "COMPB_24") (pintype "passive"))
    )
    (net (code "79") (name "unconnected-(U2-DNC-Pad10)") (class "Default")
      (node (ref "U2") (pin "10") (pinfunction "DNC_10") (pintype "passive"))
    )
    (net (code "80") (name "unconnected-(U2-GPO0-Pad25)") (class "Default")
      (node (ref "U2") (pin "25") (pinfunction "GPO0_25") (pintype "passive"))
    )
    (net (code "81") (name "unconnected-(U2-GPO1-Pad38)") (class "Default")
      (node (ref "U2") (pin "38") (pinfunction "GPO1_38") (pintype "passive"))
    )
    (net (code "82") (name "unconnected-(U2-REF+-Pad40)") (class "Default")
      (node (ref "U2") (pin "40") (pinfunction "REF+_40") (pintype "passive"))
    )
    (net (code "83") (name "unconnected-(U2-REF--Pad39)") (class "Default")
      (node (ref "U2") (pin "39") (pinfunction "REF-_39") (pintype "passive"))
    )
    (net (code "84") (name "unconnected-(U2-XTAL1-Pad12)") (class "Default")
      (node (ref "U2") (pin "12") (pinfunction "XTAL1_12") (pintype "passive"))
    )
    (net (code "85") (name "unconnected-(U2-XTAL2{slash}CLKIO-Pad13)") (class "Default")
      (node (ref "U2") (pin "13") (pinfunction "XTAL2/CLKIO_13") (pintype "passive"))
    )
    (net (code "86") (name "unconnected-(U2-~{SYNC}-Pad19)") (class "Default")
      (node (ref "U2") (pin "19") (pinfunction "~{SYNC}_19") (pintype "passive"))
    )
  )
)
